# PCB-CMB-3.net
KiCad netlist of a schematic drawn in EAGLE
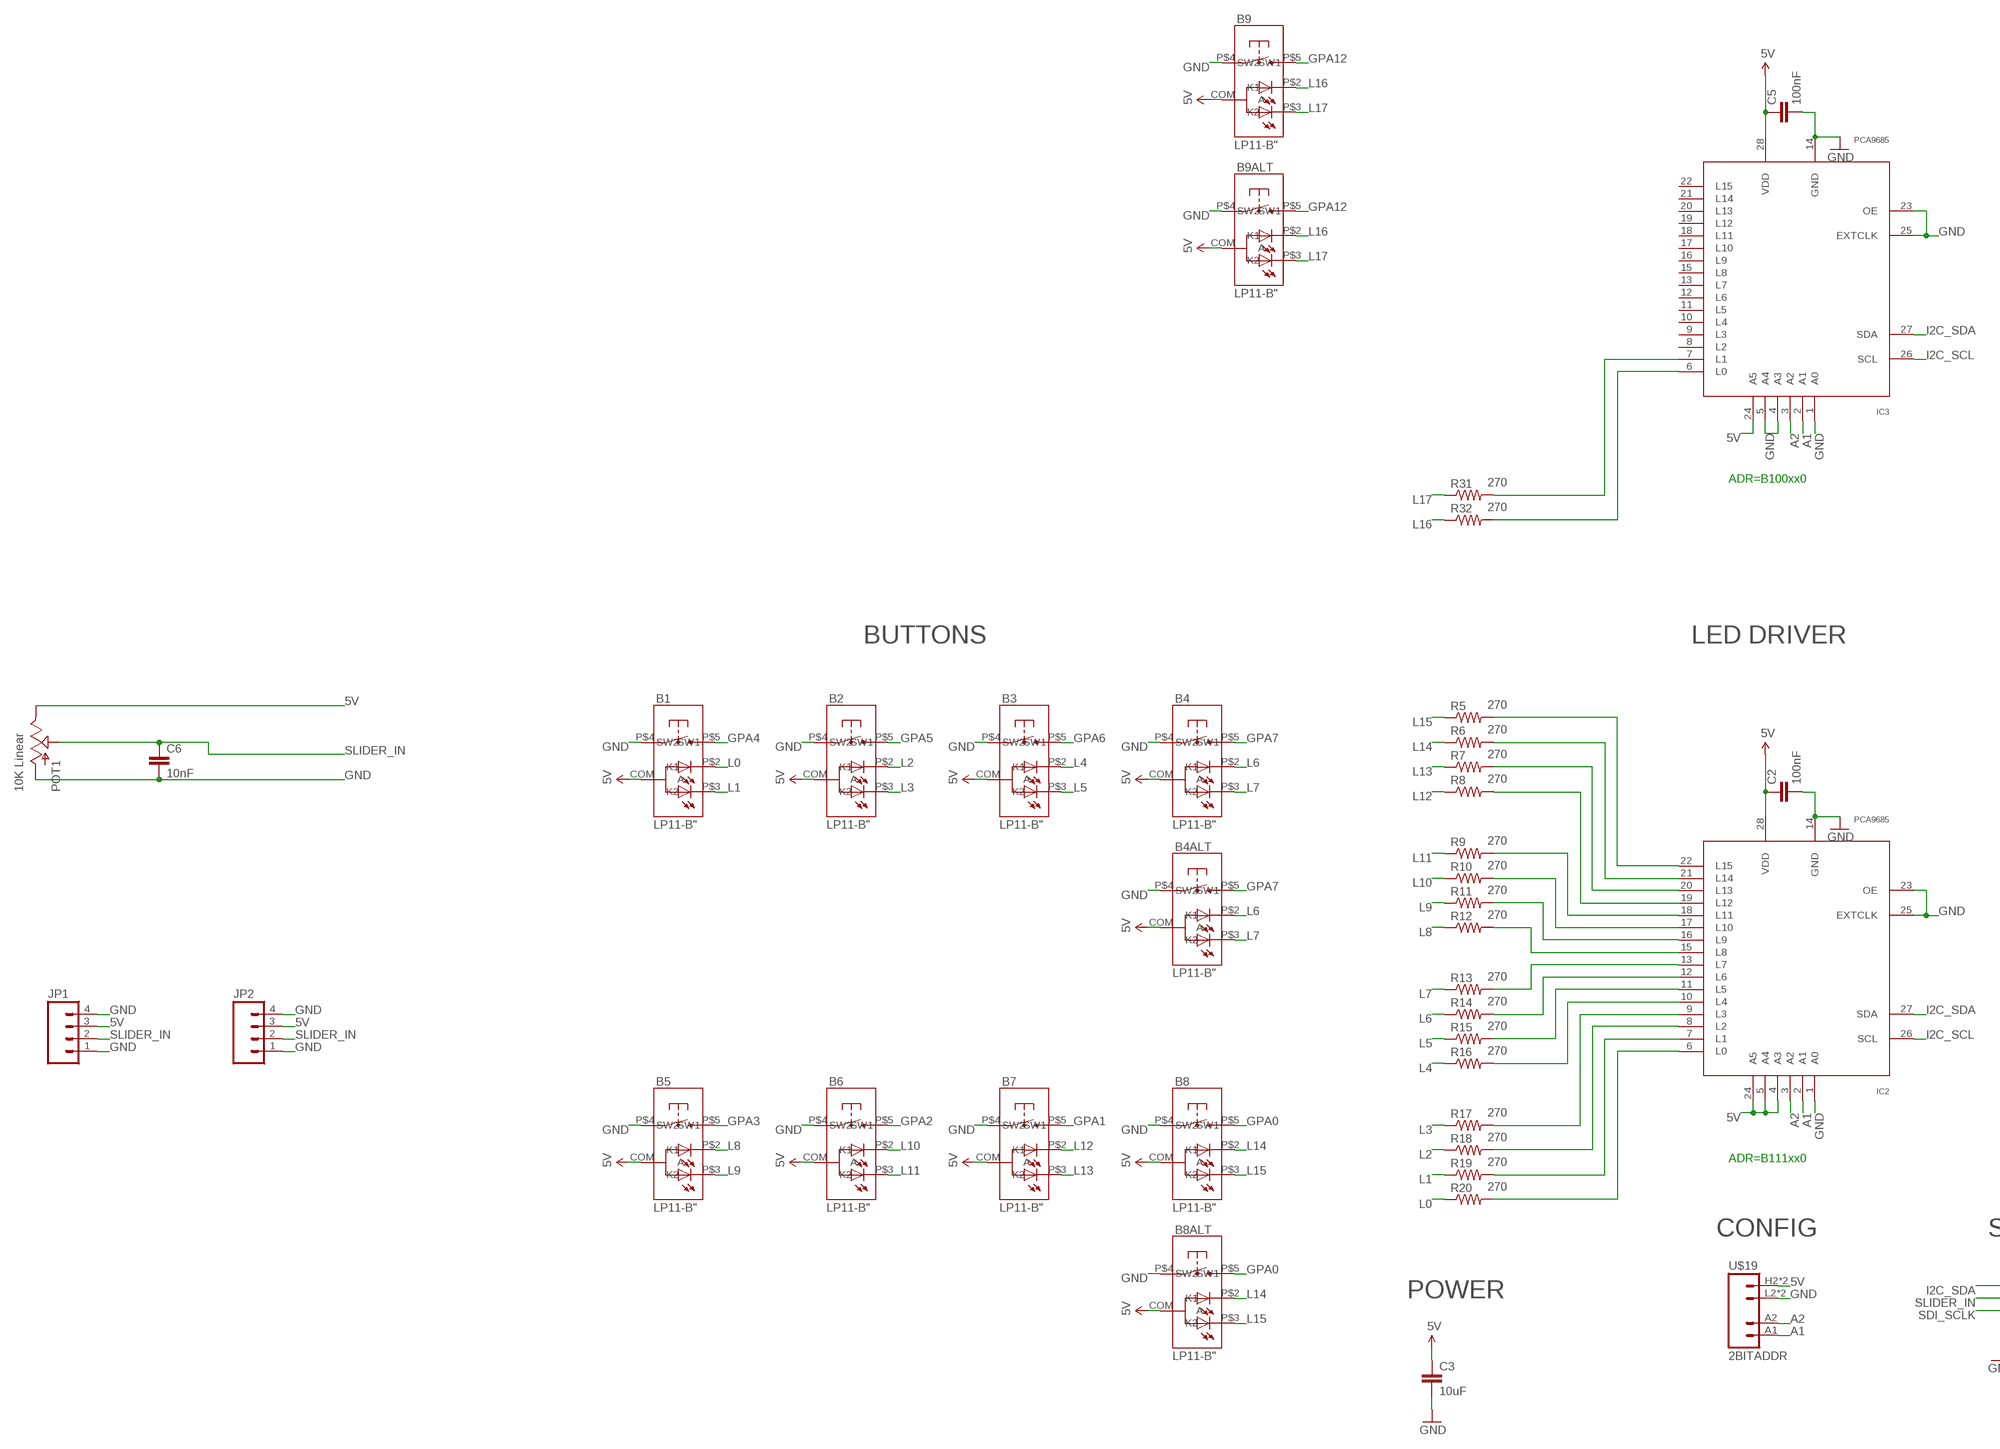
[diagram p0: schematic, sheet 1, part 1 of 2]
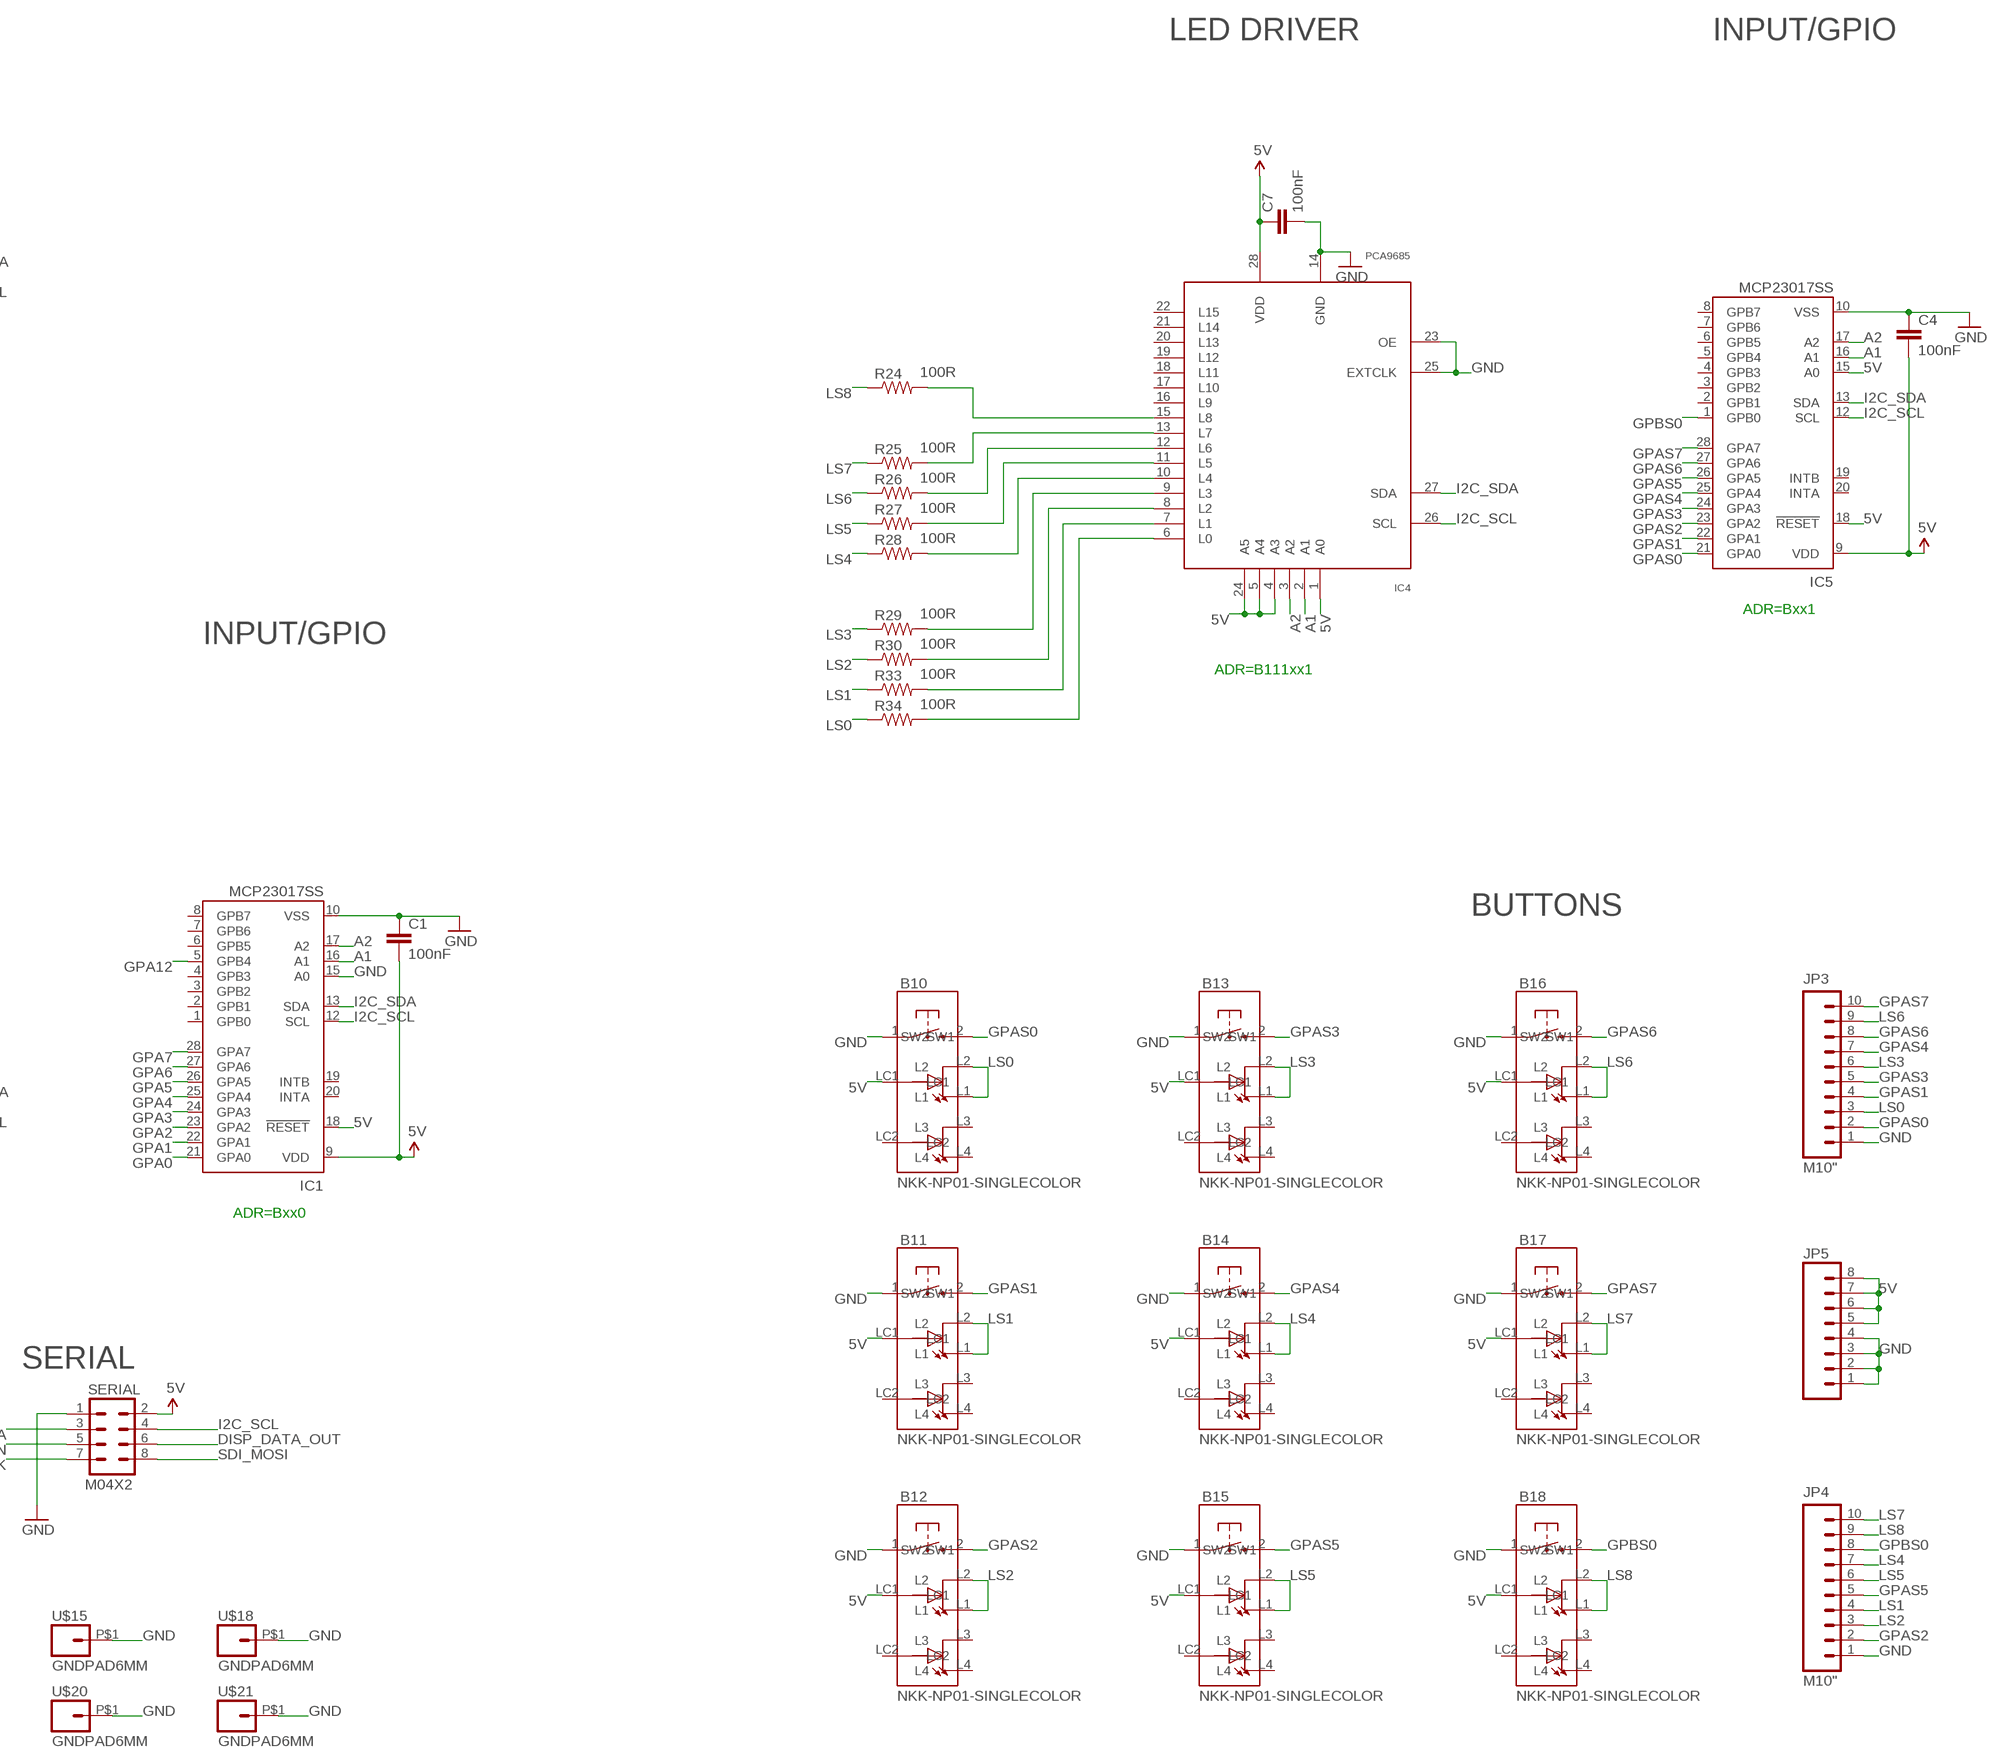
[diagram p1: schematic, sheet 1, part 2 of 2]

(export (version "E")
  (design (tool "Eeschema 10.0.6"))
  (components
    (comp (ref "B1")
      (value "LP11-B\"")
      (footprint "eagle-import:LP11")
      (libsource (lib "eagle-import") (part "LP11-B{dblquote}"))
    )
    (comp (ref "B2")
      (value "LP11-B\"")
      (footprint "eagle-import:LP11")
      (libsource (lib "eagle-import") (part "LP11-B{dblquote}"))
    )
    (comp (ref "B3")
      (value "LP11-B\"")
      (footprint "eagle-import:LP11")
      (libsource (lib "eagle-import") (part "LP11-B{dblquote}"))
    )
    (comp (ref "B4")
      (value "LP11-B\"")
      (footprint "eagle-import:LP11")
      (libsource (lib "eagle-import") (part "LP11-B{dblquote}"))
    )
    (comp (ref "B4ALT")
      (value "LP11-B\"")
      (footprint "eagle-import:LP11")
      (libsource (lib "eagle-import") (part "LP11-B{dblquote}"))
    )
    (comp (ref "B5")
      (value "LP11-B\"")
      (footprint "eagle-import:LP11")
      (libsource (lib "eagle-import") (part "LP11-B{dblquote}"))
    )
    (comp (ref "B6")
      (value "LP11-B\"")
      (footprint "eagle-import:LP11")
      (libsource (lib "eagle-import") (part "LP11-B{dblquote}"))
    )
    (comp (ref "B7")
      (value "LP11-B\"")
      (footprint "eagle-import:LP11")
      (libsource (lib "eagle-import") (part "LP11-B{dblquote}"))
    )
    (comp (ref "B8")
      (value "LP11-B\"")
      (footprint "eagle-import:LP11")
      (libsource (lib "eagle-import") (part "LP11-B{dblquote}"))
    )
    (comp (ref "B8ALT")
      (value "LP11-B\"")
      (footprint "eagle-import:LP11")
      (libsource (lib "eagle-import") (part "LP11-B{dblquote}"))
    )
    (comp (ref "B9")
      (value "LP11-B\"")
      (footprint "eagle-import:LP11")
      (libsource (lib "eagle-import") (part "LP11-B{dblquote}"))
    )
    (comp (ref "B9ALT")
      (value "LP11-B\"")
      (footprint "eagle-import:LP11")
      (libsource (lib "eagle-import") (part "LP11-B{dblquote}"))
    )
    (comp (ref "B10")
      (value "NKK-NP01-SINGLECOLOR")
      (footprint "eagle-import:NKK-NP01")
      (libsource (lib "eagle-import") (part "NKK-NP01-SINGLECOLOR"))
    )
    (comp (ref "B11")
      (value "NKK-NP01-SINGLECOLOR")
      (footprint "eagle-import:NKK-NP01")
      (libsource (lib "eagle-import") (part "NKK-NP01-SINGLECOLOR"))
    )
    (comp (ref "B12")
      (value "NKK-NP01-SINGLECOLOR")
      (footprint "eagle-import:NKK-NP01")
      (libsource (lib "eagle-import") (part "NKK-NP01-SINGLECOLOR"))
    )
    (comp (ref "B13")
      (value "NKK-NP01-SINGLECOLOR")
      (footprint "eagle-import:NKK-NP01")
      (libsource (lib "eagle-import") (part "NKK-NP01-SINGLECOLOR"))
    )
    (comp (ref "B14")
      (value "NKK-NP01-SINGLECOLOR")
      (footprint "eagle-import:NKK-NP01")
      (libsource (lib "eagle-import") (part "NKK-NP01-SINGLECOLOR"))
    )
    (comp (ref "B15")
      (value "NKK-NP01-SINGLECOLOR")
      (footprint "eagle-import:NKK-NP01")
      (libsource (lib "eagle-import") (part "NKK-NP01-SINGLECOLOR"))
    )
    (comp (ref "B16")
      (value "NKK-NP01-SINGLECOLOR")
      (footprint "eagle-import:NKK-NP01")
      (libsource (lib "eagle-import") (part "NKK-NP01-SINGLECOLOR"))
    )
    (comp (ref "B17")
      (value "NKK-NP01-SINGLECOLOR")
      (footprint "eagle-import:NKK-NP01")
      (libsource (lib "eagle-import") (part "NKK-NP01-SINGLECOLOR"))
    )
    (comp (ref "B18")
      (value "NKK-NP01-SINGLECOLOR")
      (footprint "eagle-import:NKK-NP01")
      (libsource (lib "eagle-import") (part "NKK-NP01-SINGLECOLOR"))
    )
    (comp (ref "C1")
      (value "100nF")
      (footprint "eagle-import:0603-CAP")
      (libsource (lib "eagle-import") (part "CAP0603-CAP"))
    )
    (comp (ref "C2")
      (value "100nF")
      (footprint "eagle-import:0603-CAP")
      (libsource (lib "eagle-import") (part "CAP0603-CAP"))
    )
    (comp (ref "C3")
      (value "10uF")
      (footprint "eagle-import:0805")
      (libsource (lib "eagle-import") (part "CAP0805"))
    )
    (comp (ref "C4")
      (value "100nF")
      (footprint "eagle-import:0603-CAP")
      (libsource (lib "eagle-import") (part "CAP0603-CAP"))
    )
    (comp (ref "C5")
      (value "100nF")
      (footprint "eagle-import:0603-CAP")
      (libsource (lib "eagle-import") (part "CAP0603-CAP"))
    )
    (comp (ref "C6")
      (value "10nF")
      (footprint "eagle-import:0603-CAP")
      (libsource (lib "eagle-import") (part "CAP0603-CAP"))
    )
    (comp (ref "C7")
      (value "100nF")
      (footprint "eagle-import:0603-CAP")
      (libsource (lib "eagle-import") (part "CAP0603-CAP"))
    )
    (comp (ref "IC1")
      (value "MCP23017SS")
      (footprint "eagle-import:SSOP28")
      (fields
        (field (name "MF") "MICROCHIP")
        (field (name "MPN") "MCP23017-E/SS")
        (field (name "MPN_1") "MCP23017-E/SS")
        (field (name "OC_FARNELL") "1467674")
        (field (name "OC_NEWARK") "31K2960")
      )
      (libsource (lib "eagle-import") (part "MCP23017SS"))
    )
    (comp (ref "IC2")
      (value "PCA9685")
      (footprint "eagle-import:TSSOP28")
      (libsource (lib "eagle-import") (part "PCA9685"))
    )
    (comp (ref "IC3")
      (value "PCA9685")
      (footprint "eagle-import:TSSOP28")
      (libsource (lib "eagle-import") (part "PCA9685"))
    )
    (comp (ref "IC4")
      (value "PCA9685")
      (footprint "eagle-import:TSSOP28")
      (libsource (lib "eagle-import") (part "PCA9685"))
    )
    (comp (ref "IC5")
      (value "MCP23017SS")
      (footprint "eagle-import:SSOP28")
      (fields
        (field (name "MF") "MICROCHIP")
        (field (name "MPN") "MCP23017-E/SS")
        (field (name "MPN_1") "MCP23017-E/SS")
        (field (name "OC_FARNELL") "1467674")
        (field (name "OC_NEWARK") "31K2960")
      )
      (libsource (lib "eagle-import") (part "MCP23017SS"))
    )
    (comp (ref "JP1")
      (value "M04PTH")
      (footprint "eagle-import:1X04")
      (libsource (lib "eagle-import") (part "M04PTH"))
    )
    (comp (ref "JP2")
      (value "M04PTH")
      (footprint "eagle-import:1X04")
      (libsource (lib "eagle-import") (part "M04PTH"))
    )
    (comp (ref "JP3")
      (value "M10\"")
      (footprint "eagle-import:1X10")
      (libsource (lib "eagle-import") (part "M10{dblquote}"))
    )
    (comp (ref "JP4")
      (value "M10\"")
      (footprint "eagle-import:1X10")
      (libsource (lib "eagle-import") (part "M10{dblquote}"))
    )
    (comp (ref "JP5")
      (value "M08LOCK")
      (footprint "eagle-import:1X08_LOCK")
      (libsource (lib "eagle-import") (part "M08LOCK"))
    )
    (comp (ref "POT1")
      (value "10K Linear")
      (footprint "eagle-import:SLIDER20")
      (libsource (lib "eagle-import") (part "SLIDER20"))
    )
    (comp (ref "R5")
      (value "270")
      (footprint "eagle-import:0603-RES")
      (libsource (lib "eagle-import") (part "RESISTOR0603-RES"))
    )
    (comp (ref "R6")
      (value "270")
      (footprint "eagle-import:0603-RES")
      (libsource (lib "eagle-import") (part "RESISTOR0603-RES"))
    )
    (comp (ref "R7")
      (value "270")
      (footprint "eagle-import:0603-RES")
      (libsource (lib "eagle-import") (part "RESISTOR0603-RES"))
    )
    (comp (ref "R8")
      (value "270")
      (footprint "eagle-import:0603-RES")
      (libsource (lib "eagle-import") (part "RESISTOR0603-RES"))
    )
    (comp (ref "R9")
      (value "270")
      (footprint "eagle-import:0603-RES")
      (libsource (lib "eagle-import") (part "RESISTOR0603-RES"))
    )
    (comp (ref "R10")
      (value "270")
      (footprint "eagle-import:0603-RES")
      (libsource (lib "eagle-import") (part "RESISTOR0603-RES"))
    )
    (comp (ref "R11")
      (value "270")
      (footprint "eagle-import:0603-RES")
      (libsource (lib "eagle-import") (part "RESISTOR0603-RES"))
    )
    (comp (ref "R12")
      (value "270")
      (footprint "eagle-import:0603-RES")
      (libsource (lib "eagle-import") (part "RESISTOR0603-RES"))
    )
    (comp (ref "R13")
      (value "270")
      (footprint "eagle-import:0603-RES")
      (libsource (lib "eagle-import") (part "RESISTOR0603-RES"))
    )
    (comp (ref "R14")
      (value "270")
      (footprint "eagle-import:0603-RES")
      (libsource (lib "eagle-import") (part "RESISTOR0603-RES"))
    )
    (comp (ref "R15")
      (value "270")
      (footprint "eagle-import:0603-RES")
      (libsource (lib "eagle-import") (part "RESISTOR0603-RES"))
    )
    (comp (ref "R16")
      (value "270")
      (footprint "eagle-import:0603-RES")
      (libsource (lib "eagle-import") (part "RESISTOR0603-RES"))
    )
    (comp (ref "R17")
      (value "270")
      (footprint "eagle-import:0603-RES")
      (libsource (lib "eagle-import") (part "RESISTOR0603-RES"))
    )
    (comp (ref "R18")
      (value "270")
      (footprint "eagle-import:0603-RES")
      (libsource (lib "eagle-import") (part "RESISTOR0603-RES"))
    )
    (comp (ref "R19")
      (value "270")
      (footprint "eagle-import:0603-RES")
      (libsource (lib "eagle-import") (part "RESISTOR0603-RES"))
    )
    (comp (ref "R20")
      (value "270")
      (footprint "eagle-import:0603-RES")
      (libsource (lib "eagle-import") (part "RESISTOR0603-RES"))
    )
    (comp (ref "R24")
      (value "100R")
      (footprint "eagle-import:0603-RES")
      (libsource (lib "eagle-import") (part "RESISTOR0603-RES"))
    )
    (comp (ref "R25")
      (value "100R")
      (footprint "eagle-import:0603-RES")
      (libsource (lib "eagle-import") (part "RESISTOR0603-RES"))
    )
    (comp (ref "R26")
      (value "100R")
      (footprint "eagle-import:0603-RES")
      (libsource (lib "eagle-import") (part "RESISTOR0603-RES"))
    )
    (comp (ref "R27")
      (value "100R")
      (footprint "eagle-import:0603-RES")
      (libsource (lib "eagle-import") (part "RESISTOR0603-RES"))
    )
    (comp (ref "R28")
      (value "100R")
      (footprint "eagle-import:0603-RES")
      (libsource (lib "eagle-import") (part "RESISTOR0603-RES"))
    )
    (comp (ref "R29")
      (value "100R")
      (footprint "eagle-import:0603-RES")
      (libsource (lib "eagle-import") (part "RESISTOR0603-RES"))
    )
    (comp (ref "R30")
      (value "100R")
      (footprint "eagle-import:0603-RES")
      (libsource (lib "eagle-import") (part "RESISTOR0603-RES"))
    )
    (comp (ref "R31")
      (value "270")
      (footprint "eagle-import:0603-RES")
      (libsource (lib "eagle-import") (part "RESISTOR0603-RES"))
    )
    (comp (ref "R32")
      (value "270")
      (footprint "eagle-import:0603-RES")
      (libsource (lib "eagle-import") (part "RESISTOR0603-RES"))
    )
    (comp (ref "R33")
      (value "100R")
      (footprint "eagle-import:0603-RES")
      (libsource (lib "eagle-import") (part "RESISTOR0603-RES"))
    )
    (comp (ref "R34")
      (value "100R")
      (footprint "eagle-import:0603-RES")
      (libsource (lib "eagle-import") (part "RESISTOR0603-RES"))
    )
    (comp (ref "SERIAL")
      (value "M04X2")
      (footprint "eagle-import:2X4")
      (libsource (lib "eagle-import") (part "M04X2"))
    )
    (comp (ref "U$15")
      (value "GNDPAD6MM")
      (footprint "eagle-import:3.2MMPAD6MM")
      (libsource (lib "eagle-import") (part "GNDPAD6MM"))
    )
    (comp (ref "U$18")
      (value "GNDPAD6MM")
      (footprint "eagle-import:3.2MMPAD6MM")
      (libsource (lib "eagle-import") (part "GNDPAD6MM"))
    )
    (comp (ref "U$19")
      (value "2BITADDR")
      (footprint "eagle-import:2BITADDR")
      (libsource (lib "eagle-import") (part "2BITADDR"))
    )
    (comp (ref "U$20")
      (value "GNDPAD6MM")
      (footprint "eagle-import:3.2MMPAD6MM")
      (libsource (lib "eagle-import") (part "GNDPAD6MM"))
    )
    (comp (ref "U$21")
      (value "GNDPAD6MM")
      (footprint "eagle-import:3.2MMPAD6MM")
      (libsource (lib "eagle-import") (part "GNDPAD6MM"))
    )
  )
  (nets
    (net (code "1") (name "5V") (class "Default")
      (node (ref "B1") (pin "COM") (pinfunction "A_COM") (pintype "bidirectional"))
      (node (ref "B10") (pin "LC1") (pinfunction "LC1_LC1") (pintype "bidirectional"))
      (node (ref "B11") (pin "LC1") (pinfunction "LC1_LC1") (pintype "bidirectional"))
      (node (ref "B12") (pin "LC1") (pinfunction "LC1_LC1") (pintype "bidirectional"))
      (node (ref "B13") (pin "LC1") (pinfunction "LC1_LC1") (pintype "bidirectional"))
      (node (ref "B14") (pin "LC1") (pinfunction "LC1_LC1") (pintype "bidirectional"))
      (node (ref "B15") (pin "LC1") (pinfunction "LC1_LC1") (pintype "bidirectional"))
      (node (ref "B16") (pin "LC1") (pinfunction "LC1_LC1") (pintype "bidirectional"))
      (node (ref "B17") (pin "LC1") (pinfunction "LC1_LC1") (pintype "bidirectional"))
      (node (ref "B18") (pin "LC1") (pinfunction "LC1_LC1") (pintype "bidirectional"))
      (node (ref "B2") (pin "COM") (pinfunction "A_COM") (pintype "bidirectional"))
      (node (ref "B3") (pin "COM") (pinfunction "A_COM") (pintype "bidirectional"))
      (node (ref "B4") (pin "COM") (pinfunction "A_COM") (pintype "bidirectional"))
      (node (ref "B4ALT") (pin "COM") (pinfunction "A_COM") (pintype "bidirectional"))
      (node (ref "B5") (pin "COM") (pinfunction "A_COM") (pintype "bidirectional"))
      (node (ref "B6") (pin "COM") (pinfunction "A_COM") (pintype "bidirectional"))
      (node (ref "B7") (pin "COM") (pinfunction "A_COM") (pintype "bidirectional"))
      (node (ref "B8") (pin "COM") (pinfunction "A_COM") (pintype "bidirectional"))
      (node (ref "B8ALT") (pin "COM") (pinfunction "A_COM") (pintype "bidirectional"))
      (node (ref "B9") (pin "COM") (pinfunction "A_COM") (pintype "bidirectional"))
      (node (ref "B9ALT") (pin "COM") (pinfunction "A_COM") (pintype "bidirectional"))
      (node (ref "C1") (pin "2") (pinfunction "2_2") (pintype "passive"))
      (node (ref "C2") (pin "1") (pinfunction "1_1") (pintype "passive"))
      (node (ref "C3") (pin "1") (pinfunction "1_1") (pintype "passive"))
      (node (ref "C4") (pin "2") (pinfunction "2_2") (pintype "passive"))
      (node (ref "C5") (pin "1") (pinfunction "1_1") (pintype "passive"))
      (node (ref "C7") (pin "1") (pinfunction "1_1") (pintype "passive"))
      (node (ref "IC1") (pin "18") (pinfunction "~{RESET}_18") (pintype "input"))
      (node (ref "IC1") (pin "9") (pinfunction "VDD_9") (pintype "power_in"))
      (node (ref "IC2") (pin "24") (pinfunction "A5_24") (pintype "input"))
      (node (ref "IC2") (pin "28") (pinfunction "VDD_28") (pintype "power_in"))
      (node (ref "IC2") (pin "4") (pinfunction "A3_4") (pintype "input"))
      (node (ref "IC2") (pin "5") (pinfunction "A4_5") (pintype "input"))
      (node (ref "IC3") (pin "24") (pinfunction "A5_24") (pintype "input"))
      (node (ref "IC3") (pin "28") (pinfunction "VDD_28") (pintype "power_in"))
      (node (ref "IC4") (pin "1") (pinfunction "A0_1") (pintype "input"))
      (node (ref "IC4") (pin "24") (pinfunction "A5_24") (pintype "input"))
      (node (ref "IC4") (pin "28") (pinfunction "VDD_28") (pintype "power_in"))
      (node (ref "IC4") (pin "4") (pinfunction "A3_4") (pintype "input"))
      (node (ref "IC4") (pin "5") (pinfunction "A4_5") (pintype "input"))
      (node (ref "IC5") (pin "15") (pinfunction "A0_15") (pintype "input"))
      (node (ref "IC5") (pin "18") (pinfunction "~{RESET}_18") (pintype "input"))
      (node (ref "IC5") (pin "9") (pinfunction "VDD_9") (pintype "power_in"))
      (node (ref "JP1") (pin "3") (pinfunction "3_3") (pintype "passive"))
      (node (ref "JP2") (pin "3") (pinfunction "3_3") (pintype "passive"))
      (node (ref "JP5") (pin "5") (pinfunction "5_5") (pintype "passive"))
      (node (ref "JP5") (pin "6") (pinfunction "6_6") (pintype "passive"))
      (node (ref "JP5") (pin "7") (pinfunction "7_7") (pintype "passive"))
      (node (ref "JP5") (pin "8") (pinfunction "8_8") (pintype "passive"))
      (node (ref "POT1") (pin "1") (pinfunction "E_1") (pintype "passive"))
      (node (ref "SERIAL") (pin "2") (pinfunction "2_2") (pintype "passive"))
      (node (ref "U$19") (pin "H2") (pinfunction "VCC_H2") (pintype "passive"))
      (node (ref "U$19") (pin "H3") (pinfunction "VCC_H3") (pintype "passive"))
    )
    (net (code "2") (name "A1") (class "Default")
      (node (ref "IC1") (pin "16") (pinfunction "A1_16") (pintype "input"))
      (node (ref "IC2") (pin "2") (pinfunction "A1_2") (pintype "input"))
      (node (ref "IC3") (pin "2") (pinfunction "A1_2") (pintype "input"))
      (node (ref "IC4") (pin "2") (pinfunction "A1_2") (pintype "input"))
      (node (ref "IC5") (pin "16") (pinfunction "A1_16") (pintype "input"))
      (node (ref "U$19") (pin "A1") (pinfunction "A1_A1") (pintype "passive"))
    )
    (net (code "3") (name "A2") (class "Default")
      (node (ref "IC1") (pin "17") (pinfunction "A2_17") (pintype "input"))
      (node (ref "IC2") (pin "3") (pinfunction "A2_3") (pintype "input"))
      (node (ref "IC3") (pin "3") (pinfunction "A2_3") (pintype "input"))
      (node (ref "IC4") (pin "3") (pinfunction "A2_3") (pintype "input"))
      (node (ref "IC5") (pin "17") (pinfunction "A2_17") (pintype "input"))
      (node (ref "U$19") (pin "A2") (pinfunction "A2_A2") (pintype "passive"))
    )
    (net (code "4") (name "DISP_DATA_OUT") (class "Default")
      (node (ref "SERIAL") (pin "6") (pinfunction "6_6") (pintype "passive"))
    )
    (net (code "5") (name "GND") (class "Default")
      (node (ref "B1") (pin "P$4") (pinfunction "SW1_P$4") (pintype "bidirectional"))
      (node (ref "B10") (pin "1") (pinfunction "SW1_1") (pintype "bidirectional"))
      (node (ref "B11") (pin "1") (pinfunction "SW1_1") (pintype "bidirectional"))
      (node (ref "B12") (pin "1") (pinfunction "SW1_1") (pintype "bidirectional"))
      (node (ref "B13") (pin "1") (pinfunction "SW1_1") (pintype "bidirectional"))
      (node (ref "B14") (pin "1") (pinfunction "SW1_1") (pintype "bidirectional"))
      (node (ref "B15") (pin "1") (pinfunction "SW1_1") (pintype "bidirectional"))
      (node (ref "B16") (pin "1") (pinfunction "SW1_1") (pintype "bidirectional"))
      (node (ref "B17") (pin "1") (pinfunction "SW1_1") (pintype "bidirectional"))
      (node (ref "B18") (pin "1") (pinfunction "SW1_1") (pintype "bidirectional"))
      (node (ref "B2") (pin "P$4") (pinfunction "SW1_P$4") (pintype "bidirectional"))
      (node (ref "B3") (pin "P$4") (pinfunction "SW1_P$4") (pintype "bidirectional"))
      (node (ref "B4") (pin "P$4") (pinfunction "SW1_P$4") (pintype "bidirectional"))
      (node (ref "B4ALT") (pin "P$4") (pinfunction "SW1_P$4") (pintype "bidirectional"))
      (node (ref "B5") (pin "P$4") (pinfunction "SW1_P$4") (pintype "bidirectional"))
      (node (ref "B6") (pin "P$4") (pinfunction "SW1_P$4") (pintype "bidirectional"))
      (node (ref "B7") (pin "P$4") (pinfunction "SW1_P$4") (pintype "bidirectional"))
      (node (ref "B8") (pin "P$4") (pinfunction "SW1_P$4") (pintype "bidirectional"))
      (node (ref "B8ALT") (pin "P$4") (pinfunction "SW1_P$4") (pintype "bidirectional"))
      (node (ref "B9") (pin "P$4") (pinfunction "SW1_P$4") (pintype "bidirectional"))
      (node (ref "B9ALT") (pin "P$4") (pinfunction "SW1_P$4") (pintype "bidirectional"))
      (node (ref "C1") (pin "1") (pinfunction "1_1") (pintype "passive"))
      (node (ref "C2") (pin "2") (pinfunction "2_2") (pintype "passive"))
      (node (ref "C3") (pin "2") (pinfunction "2_2") (pintype "passive"))
      (node (ref "C4") (pin "1") (pinfunction "1_1") (pintype "passive"))
      (node (ref "C5") (pin "2") (pinfunction "2_2") (pintype "passive"))
      (node (ref "C6") (pin "2") (pinfunction "2_2") (pintype "passive"))
      (node (ref "C7") (pin "2") (pinfunction "2_2") (pintype "passive"))
      (node (ref "IC1") (pin "10") (pinfunction "VSS_10") (pintype "power_in"))
      (node (ref "IC1") (pin "15") (pinfunction "A0_15") (pintype "input"))
      (node (ref "IC2") (pin "1") (pinfunction "A0_1") (pintype "input"))
      (node (ref "IC2") (pin "14") (pinfunction "GND_14") (pintype "power_in"))
      (node (ref "IC2") (pin "23") (pinfunction "OE_23") (pintype "input"))
      (node (ref "IC2") (pin "25") (pinfunction "EXTCLK_25") (pintype "input"))
      (node (ref "IC3") (pin "1") (pinfunction "A0_1") (pintype "input"))
      (node (ref "IC3") (pin "14") (pinfunction "GND_14") (pintype "power_in"))
      (node (ref "IC3") (pin "23") (pinfunction "OE_23") (pintype "input"))
      (node (ref "IC3") (pin "25") (pinfunction "EXTCLK_25") (pintype "input"))
      (node (ref "IC3") (pin "4") (pinfunction "A3_4") (pintype "input"))
      (node (ref "IC3") (pin "5") (pinfunction "A4_5") (pintype "input"))
      (node (ref "IC4") (pin "14") (pinfunction "GND_14") (pintype "power_in"))
      (node (ref "IC4") (pin "23") (pinfunction "OE_23") (pintype "input"))
      (node (ref "IC4") (pin "25") (pinfunction "EXTCLK_25") (pintype "input"))
      (node (ref "IC5") (pin "10") (pinfunction "VSS_10") (pintype "power_in"))
      (node (ref "JP1") (pin "1") (pinfunction "1_1") (pintype "passive"))
      (node (ref "JP1") (pin "4") (pinfunction "4_4") (pintype "passive"))
      (node (ref "JP2") (pin "1") (pinfunction "1_1") (pintype "passive"))
      (node (ref "JP2") (pin "4") (pinfunction "4_4") (pintype "passive"))
      (node (ref "JP3") (pin "1") (pinfunction "1_1") (pintype "passive"))
      (node (ref "JP4") (pin "1") (pinfunction "1_1") (pintype "passive"))
      (node (ref "JP5") (pin "1") (pinfunction "1_1") (pintype "passive"))
      (node (ref "JP5") (pin "2") (pinfunction "2_2") (pintype "passive"))
      (node (ref "JP5") (pin "3") (pinfunction "3_3") (pintype "passive"))
      (node (ref "JP5") (pin "4") (pinfunction "4_4") (pintype "passive"))
      (node (ref "POT1") (pin "3") (pinfunction "A_3") (pintype "passive"))
      (node (ref "SERIAL") (pin "1") (pinfunction "1_1") (pintype "passive"))
      (node (ref "U$15") (pin "P$1") (pinfunction "1_P$1") (pintype "passive"))
      (node (ref "U$18") (pin "P$1") (pinfunction "1_P$1") (pintype "passive"))
      (node (ref "U$19") (pin "L2") (pinfunction "GND_L2") (pintype "passive"))
      (node (ref "U$19") (pin "L3") (pinfunction "GND_L3") (pintype "passive"))
      (node (ref "U$20") (pin "P$1") (pinfunction "1_P$1") (pintype "passive"))
      (node (ref "U$21") (pin "P$1") (pinfunction "1_P$1") (pintype "passive"))
    )
    (net (code "6") (name "GPA0") (class "Default")
      (node (ref "B8") (pin "P$5") (pinfunction "SW2_P$5") (pintype "bidirectional"))
      (node (ref "B8ALT") (pin "P$5") (pinfunction "SW2_P$5") (pintype "bidirectional"))
      (node (ref "IC1") (pin "21") (pinfunction "GPA0_21") (pintype "bidirectional"))
    )
    (net (code "7") (name "GPA1") (class "Default")
      (node (ref "B7") (pin "P$5") (pinfunction "SW2_P$5") (pintype "bidirectional"))
      (node (ref "IC1") (pin "22") (pinfunction "GPA1_22") (pintype "bidirectional"))
    )
    (net (code "8") (name "GPA2") (class "Default")
      (node (ref "B6") (pin "P$5") (pinfunction "SW2_P$5") (pintype "bidirectional"))
      (node (ref "IC1") (pin "23") (pinfunction "GPA2_23") (pintype "bidirectional"))
    )
    (net (code "9") (name "GPA3") (class "Default")
      (node (ref "B5") (pin "P$5") (pinfunction "SW2_P$5") (pintype "bidirectional"))
      (node (ref "IC1") (pin "24") (pinfunction "GPA3_24") (pintype "bidirectional"))
    )
    (net (code "10") (name "GPA4") (class "Default")
      (node (ref "B1") (pin "P$5") (pinfunction "SW2_P$5") (pintype "bidirectional"))
      (node (ref "IC1") (pin "25") (pinfunction "GPA4_25") (pintype "bidirectional"))
    )
    (net (code "11") (name "GPA5") (class "Default")
      (node (ref "B2") (pin "P$5") (pinfunction "SW2_P$5") (pintype "bidirectional"))
      (node (ref "IC1") (pin "26") (pinfunction "GPA5_26") (pintype "bidirectional"))
    )
    (net (code "12") (name "GPA6") (class "Default")
      (node (ref "B3") (pin "P$5") (pinfunction "SW2_P$5") (pintype "bidirectional"))
      (node (ref "IC1") (pin "27") (pinfunction "GPA6_27") (pintype "bidirectional"))
    )
    (net (code "13") (name "GPA7") (class "Default")
      (node (ref "B4") (pin "P$5") (pinfunction "SW2_P$5") (pintype "bidirectional"))
      (node (ref "B4ALT") (pin "P$5") (pinfunction "SW2_P$5") (pintype "bidirectional"))
      (node (ref "IC1") (pin "28") (pinfunction "GPA7_28") (pintype "bidirectional"))
    )
    (net (code "14") (name "GPA12") (class "Default")
      (node (ref "B9") (pin "P$5") (pinfunction "SW2_P$5") (pintype "bidirectional"))
      (node (ref "B9ALT") (pin "P$5") (pinfunction "SW2_P$5") (pintype "bidirectional"))
      (node (ref "IC1") (pin "5") (pinfunction "GPB4_5") (pintype "bidirectional"))
    )
    (net (code "15") (name "GPAS0") (class "Default")
      (node (ref "B10") (pin "2") (pinfunction "SW2_2") (pintype "bidirectional"))
      (node (ref "IC5") (pin "21") (pinfunction "GPA0_21") (pintype "bidirectional"))
      (node (ref "JP3") (pin "2") (pinfunction "2_2") (pintype "passive"))
    )
    (net (code "16") (name "GPAS1") (class "Default")
      (node (ref "B11") (pin "2") (pinfunction "SW2_2") (pintype "bidirectional"))
      (node (ref "IC5") (pin "22") (pinfunction "GPA1_22") (pintype "bidirectional"))
      (node (ref "JP3") (pin "4") (pinfunction "4_4") (pintype "passive"))
    )
    (net (code "17") (name "GPAS2") (class "Default")
      (node (ref "B12") (pin "2") (pinfunction "SW2_2") (pintype "bidirectional"))
      (node (ref "IC5") (pin "23") (pinfunction "GPA2_23") (pintype "bidirectional"))
      (node (ref "JP4") (pin "2") (pinfunction "2_2") (pintype "passive"))
    )
    (net (code "18") (name "GPAS3") (class "Default")
      (node (ref "B13") (pin "2") (pinfunction "SW2_2") (pintype "bidirectional"))
      (node (ref "IC5") (pin "24") (pinfunction "GPA3_24") (pintype "bidirectional"))
      (node (ref "JP3") (pin "5") (pinfunction "5_5") (pintype "passive"))
    )
    (net (code "19") (name "GPAS4") (class "Default")
      (node (ref "B14") (pin "2") (pinfunction "SW2_2") (pintype "bidirectional"))
      (node (ref "IC5") (pin "25") (pinfunction "GPA4_25") (pintype "bidirectional"))
      (node (ref "JP3") (pin "7") (pinfunction "7_7") (pintype "passive"))
    )
    (net (code "20") (name "GPAS5") (class "Default")
      (node (ref "B15") (pin "2") (pinfunction "SW2_2") (pintype "bidirectional"))
      (node (ref "IC5") (pin "26") (pinfunction "GPA5_26") (pintype "bidirectional"))
      (node (ref "JP4") (pin "5") (pinfunction "5_5") (pintype "passive"))
    )
    (net (code "21") (name "GPAS6") (class "Default")
      (node (ref "B16") (pin "2") (pinfunction "SW2_2") (pintype "bidirectional"))
      (node (ref "IC5") (pin "27") (pinfunction "GPA6_27") (pintype "bidirectional"))
      (node (ref "JP3") (pin "8") (pinfunction "8_8") (pintype "passive"))
    )
    (net (code "22") (name "GPAS7") (class "Default")
      (node (ref "B17") (pin "2") (pinfunction "SW2_2") (pintype "bidirectional"))
      (node (ref "IC5") (pin "28") (pinfunction "GPA7_28") (pintype "bidirectional"))
      (node (ref "JP3") (pin "10") (pinfunction "10_10") (pintype "passive"))
    )
    (net (code "23") (name "GPBS0") (class "Default")
      (node (ref "B18") (pin "2") (pinfunction "SW2_2") (pintype "bidirectional"))
      (node (ref "IC5") (pin "1") (pinfunction "GPB0_1") (pintype "bidirectional"))
      (node (ref "JP4") (pin "8") (pinfunction "8_8") (pintype "passive"))
    )
    (net (code "24") (name "I2C_SCL") (class "Default")
      (node (ref "IC1") (pin "12") (pinfunction "SCL_12") (pintype "input"))
      (node (ref "IC2") (pin "26") (pinfunction "SCL_26") (pintype "input"))
      (node (ref "IC3") (pin "26") (pinfunction "SCL_26") (pintype "input"))
      (node (ref "IC4") (pin "26") (pinfunction "SCL_26") (pintype "input"))
      (node (ref "IC5") (pin "12") (pinfunction "SCL_12") (pintype "input"))
      (node (ref "SERIAL") (pin "4") (pinfunction "4_4") (pintype "passive"))
    )
    (net (code "25") (name "I2C_SDA") (class "Default")
      (node (ref "IC1") (pin "13") (pinfunction "SDA_13") (pintype "bidirectional"))
      (node (ref "IC2") (pin "27") (pinfunction "SDA_27") (pintype "input"))
      (node (ref "IC3") (pin "27") (pinfunction "SDA_27") (pintype "input"))
      (node (ref "IC4") (pin "27") (pinfunction "SDA_27") (pintype "input"))
      (node (ref "IC5") (pin "13") (pinfunction "SDA_13") (pintype "bidirectional"))
      (node (ref "SERIAL") (pin "3") (pinfunction "3_3") (pintype "passive"))
    )
    (net (code "26") (name "L0") (class "Default")
      (node (ref "B1") (pin "P$2") (pinfunction "K1_P$2") (pintype "bidirectional"))
      (node (ref "R20") (pin "1") (pinfunction "1_1") (pintype "passive"))
    )
    (net (code "27") (name "L1") (class "Default")
      (node (ref "B1") (pin "P$3") (pinfunction "K2_P$3") (pintype "bidirectional"))
      (node (ref "R19") (pin "1") (pinfunction "1_1") (pintype "passive"))
    )
    (net (code "28") (name "L2") (class "Default")
      (node (ref "B2") (pin "P$2") (pinfunction "K1_P$2") (pintype "bidirectional"))
      (node (ref "R18") (pin "1") (pinfunction "1_1") (pintype "passive"))
    )
    (net (code "29") (name "L3") (class "Default")
      (node (ref "B2") (pin "P$3") (pinfunction "K2_P$3") (pintype "bidirectional"))
      (node (ref "R17") (pin "1") (pinfunction "1_1") (pintype "passive"))
    )
    (net (code "30") (name "L4") (class "Default")
      (node (ref "B3") (pin "P$2") (pinfunction "K1_P$2") (pintype "bidirectional"))
      (node (ref "R16") (pin "1") (pinfunction "1_1") (pintype "passive"))
    )
    (net (code "31") (name "L5") (class "Default")
      (node (ref "B3") (pin "P$3") (pinfunction "K2_P$3") (pintype "bidirectional"))
      (node (ref "R15") (pin "1") (pinfunction "1_1") (pintype "passive"))
    )
    (net (code "32") (name "L6") (class "Default")
      (node (ref "B4") (pin "P$2") (pinfunction "K1_P$2") (pintype "bidirectional"))
      (node (ref "B4ALT") (pin "P$2") (pinfunction "K1_P$2") (pintype "bidirectional"))
      (node (ref "R14") (pin "1") (pinfunction "1_1") (pintype "passive"))
    )
    (net (code "33") (name "L7") (class "Default")
      (node (ref "B4") (pin "P$3") (pinfunction "K2_P$3") (pintype "bidirectional"))
      (node (ref "B4ALT") (pin "P$3") (pinfunction "K2_P$3") (pintype "bidirectional"))
      (node (ref "R13") (pin "1") (pinfunction "1_1") (pintype "passive"))
    )
    (net (code "34") (name "L8") (class "Default")
      (node (ref "B5") (pin "P$2") (pinfunction "K1_P$2") (pintype "bidirectional"))
      (node (ref "R12") (pin "1") (pinfunction "1_1") (pintype "passive"))
    )
    (net (code "35") (name "L9") (class "Default")
      (node (ref "B5") (pin "P$3") (pinfunction "K2_P$3") (pintype "bidirectional"))
      (node (ref "R11") (pin "1") (pinfunction "1_1") (pintype "passive"))
    )
    (net (code "36") (name "L10") (class "Default")
      (node (ref "B6") (pin "P$2") (pinfunction "K1_P$2") (pintype "bidirectional"))
      (node (ref "R10") (pin "1") (pinfunction "1_1") (pintype "passive"))
    )
    (net (code "37") (name "L11") (class "Default")
      (node (ref "B6") (pin "P$3") (pinfunction "K2_P$3") (pintype "bidirectional"))
      (node (ref "R9") (pin "1") (pinfunction "1_1") (pintype "passive"))
    )
    (net (code "38") (name "L12") (class "Default")
      (node (ref "B7") (pin "P$2") (pinfunction "K1_P$2") (pintype "bidirectional"))
      (node (ref "R8") (pin "1") (pinfunction "1_1") (pintype "passive"))
    )
    (net (code "39") (name "L13") (class "Default")
      (node (ref "B7") (pin "P$3") (pinfunction "K2_P$3") (pintype "bidirectional"))
      (node (ref "R7") (pin "1") (pinfunction "1_1") (pintype "passive"))
    )
    (net (code "40") (name "L14") (class "Default")
      (node (ref "B8") (pin "P$2") (pinfunction "K1_P$2") (pintype "bidirectional"))
      (node (ref "B8ALT") (pin "P$2") (pinfunction "K1_P$2") (pintype "bidirectional"))
      (node (ref "R6") (pin "1") (pinfunction "1_1") (pintype "passive"))
    )
    (net (code "41") (name "L15") (class "Default")
      (node (ref "B8") (pin "P$3") (pinfunction "K2_P$3") (pintype "bidirectional"))
      (node (ref "B8ALT") (pin "P$3") (pinfunction "K2_P$3") (pintype "bidirectional"))
      (node (ref "R5") (pin "1") (pinfunction "1_1") (pintype "passive"))
    )
    (net (code "42") (name "L16") (class "Default")
      (node (ref "B9") (pin "P$2") (pinfunction "K1_P$2") (pintype "bidirectional"))
      (node (ref "B9ALT") (pin "P$2") (pinfunction "K1_P$2") (pintype "bidirectional"))
      (node (ref "R32") (pin "1") (pinfunction "1_1") (pintype "passive"))
    )
    (net (code "43") (name "L17") (class "Default")
      (node (ref "B9") (pin "P$3") (pinfunction "K2_P$3") (pintype "bidirectional"))
      (node (ref "B9ALT") (pin "P$3") (pinfunction "K2_P$3") (pintype "bidirectional"))
      (node (ref "R31") (pin "1") (pinfunction "1_1") (pintype "passive"))
    )
    (net (code "44") (name "LS0") (class "Default")
      (node (ref "B10") (pin "L1") (pinfunction "L1_L1") (pintype "bidirectional"))
      (node (ref "B10") (pin "L2") (pinfunction "L2_L2") (pintype "bidirectional"))
      (node (ref "JP3") (pin "3") (pinfunction "3_3") (pintype "passive"))
      (node (ref "R34") (pin "1") (pinfunction "1_1") (pintype "passive"))
    )
    (net (code "45") (name "LS1") (class "Default")
      (node (ref "B11") (pin "L1") (pinfunction "L1_L1") (pintype "bidirectional"))
      (node (ref "B11") (pin "L2") (pinfunction "L2_L2") (pintype "bidirectional"))
      (node (ref "JP4") (pin "4") (pinfunction "4_4") (pintype "passive"))
      (node (ref "R33") (pin "1") (pinfunction "1_1") (pintype "passive"))
    )
    (net (code "46") (name "LS2") (class "Default")
      (node (ref "B12") (pin "L1") (pinfunction "L1_L1") (pintype "bidirectional"))
      (node (ref "B12") (pin "L2") (pinfunction "L2_L2") (pintype "bidirectional"))
      (node (ref "JP4") (pin "3") (pinfunction "3_3") (pintype "passive"))
      (node (ref "R30") (pin "1") (pinfunction "1_1") (pintype "passive"))
    )
    (net (code "47") (name "LS3") (class "Default")
      (node (ref "B13") (pin "L1") (pinfunction "L1_L1") (pintype "bidirectional"))
      (node (ref "B13") (pin "L2") (pinfunction "L2_L2") (pintype "bidirectional"))
      (node (ref "JP3") (pin "6") (pinfunction "6_6") (pintype "passive"))
      (node (ref "R29") (pin "1") (pinfunction "1_1") (pintype "passive"))
    )
    (net (code "48") (name "LS4") (class "Default")
      (node (ref "B14") (pin "L1") (pinfunction "L1_L1") (pintype "bidirectional"))
      (node (ref "B14") (pin "L2") (pinfunction "L2_L2") (pintype "bidirectional"))
      (node (ref "JP4") (pin "7") (pinfunction "7_7") (pintype "passive"))
      (node (ref "R28") (pin "1") (pinfunction "1_1") (pintype "passive"))
    )
    (net (code "49") (name "LS5") (class "Default")
      (node (ref "B15") (pin "L1") (pinfunction "L1_L1") (pintype "bidirectional"))
      (node (ref "B15") (pin "L2") (pinfunction "L2_L2") (pintype "bidirectional"))
      (node (ref "JP4") (pin "6") (pinfunction "6_6") (pintype "passive"))
      (node (ref "R27") (pin "1") (pinfunction "1_1") (pintype "passive"))
    )
    (net (code "50") (name "LS6") (class "Default")
      (node (ref "B16") (pin "L1") (pinfunction "L1_L1") (pintype "bidirectional"))
      (node (ref "B16") (pin "L2") (pinfunction "L2_L2") (pintype "bidirectional"))
      (node (ref "JP3") (pin "9") (pinfunction "9_9") (pintype "passive"))
      (node (ref "R26") (pin "1") (pinfunction "1_1") (pintype "passive"))
    )
    (net (code "51") (name "LS7") (class "Default")
      (node (ref "B17") (pin "L1") (pinfunction "L1_L1") (pintype "bidirectional"))
      (node (ref "B17") (pin "L2") (pinfunction "L2_L2") (pintype "bidirectional"))
      (node (ref "JP4") (pin "10") (pinfunction "10_10") (pintype "passive"))
      (node (ref "R25") (pin "1") (pinfunction "1_1") (pintype "passive"))
    )
    (net (code "52") (name "LS8") (class "Default")
      (node (ref "B18") (pin "L1") (pinfunction "L1_L1") (pintype "bidirectional"))
      (node (ref "B18") (pin "L2") (pinfunction "L2_L2") (pintype "bidirectional"))
      (node (ref "JP4") (pin "9") (pinfunction "9_9") (pintype "passive"))
      (node (ref "R24") (pin "1") (pinfunction "1_1") (pintype "passive"))
    )
    (net (code "53") (name "Net-(IC2-L0)") (class "Default")
      (node (ref "IC2") (pin "6") (pinfunction "L0_6") (pintype "output"))
      (node (ref "R20") (pin "2") (pinfunction "2_2") (pintype "passive"))
    )
    (net (code "54") (name "Net-(IC2-L1)") (class "Default")
      (node (ref "IC2") (pin "7") (pinfunction "L1_7") (pintype "output"))
      (node (ref "R19") (pin "2") (pinfunction "2_2") (pintype "passive"))
    )
    (net (code "55") (name "Net-(IC2-L2)") (class "Default")
      (node (ref "IC2") (pin "8") (pinfunction "L2_8") (pintype "output"))
      (node (ref "R18") (pin "2") (pinfunction "2_2") (pintype "passive"))
    )
    (net (code "56") (name "Net-(IC2-L3)") (class "Default")
      (node (ref "IC2") (pin "9") (pinfunction "L3_9") (pintype "output"))
      (node (ref "R17") (pin "2") (pinfunction "2_2") (pintype "passive"))
    )
    (net (code "57") (name "Net-(IC2-L4)") (class "Default")
      (node (ref "IC2") (pin "10") (pinfunction "L4_10") (pintype "output"))
      (node (ref "R16") (pin "2") (pinfunction "2_2") (pintype "passive"))
    )
    (net (code "58") (name "Net-(IC2-L5)") (class "Default")
      (node (ref "IC2") (pin "11") (pinfunction "L5_11") (pintype "output"))
      (node (ref "R15") (pin "2") (pinfunction "2_2") (pintype "passive"))
    )
    (net (code "59") (name "Net-(IC2-L6)") (class "Default")
      (node (ref "IC2") (pin "12") (pinfunction "L6_12") (pintype "output"))
      (node (ref "R14") (pin "2") (pinfunction "2_2") (pintype "passive"))
    )
    (net (code "60") (name "Net-(IC2-L7)") (class "Default")
      (node (ref "IC2") (pin "13") (pinfunction "L7_13") (pintype "output"))
      (node (ref "R13") (pin "2") (pinfunction "2_2") (pintype "passive"))
    )
    (net (code "61") (name "Net-(IC2-L8)") (class "Default")
      (node (ref "IC2") (pin "15") (pinfunction "L8_15") (pintype "output"))
      (node (ref "R12") (pin "2") (pinfunction "2_2") (pintype "passive"))
    )
    (net (code "62") (name "Net-(IC2-L9)") (class "Default")
      (node (ref "IC2") (pin "16") (pinfunction "L9_16") (pintype "output"))
      (node (ref "R11") (pin "2") (pinfunction "2_2") (pintype "passive"))
    )
    (net (code "63") (name "Net-(IC2-L10)") (class "Default")
      (node (ref "IC2") (pin "17") (pinfunction "L10_17") (pintype "output"))
      (node (ref "R10") (pin "2") (pinfunction "2_2") (pintype "passive"))
    )
    (net (code "64") (name "Net-(IC2-L11)") (class "Default")
      (node (ref "IC2") (pin "18") (pinfunction "L11_18") (pintype "output"))
      (node (ref "R9") (pin "2") (pinfunction "2_2") (pintype "passive"))
    )
    (net (code "65") (name "Net-(IC2-L12)") (class "Default")
      (node (ref "IC2") (pin "19") (pinfunction "L12_19") (pintype "output"))
      (node (ref "R8") (pin "2") (pinfunction "2_2") (pintype "passive"))
    )
    (net (code "66") (name "Net-(IC2-L13)") (class "Default")
      (node (ref "IC2") (pin "20") (pinfunction "L13_20") (pintype "output"))
      (node (ref "R7") (pin "2") (pinfunction "2_2") (pintype "passive"))
    )
    (net (code "67") (name "Net-(IC2-L14)") (class "Default")
      (node (ref "IC2") (pin "21") (pinfunction "L14_21") (pintype "output"))
      (node (ref "R6") (pin "2") (pinfunction "2_2") (pintype "passive"))
    )
    (net (code "68") (name "Net-(IC2-L15)") (class "Default")
      (node (ref "IC2") (pin "22") (pinfunction "L15_22") (pintype "output"))
      (node (ref "R5") (pin "2") (pinfunction "2_2") (pintype "passive"))
    )
    (net (code "69") (name "Net-(IC3-L0)") (class "Default")
      (node (ref "IC3") (pin "6") (pinfunction "L0_6") (pintype "output"))
      (node (ref "R32") (pin "2") (pinfunction "2_2") (pintype "passive"))
    )
    (net (code "70") (name "Net-(IC3-L1)") (class "Default")
      (node (ref "IC3") (pin "7") (pinfunction "L1_7") (pintype "output"))
      (node (ref "R31") (pin "2") (pinfunction "2_2") (pintype "passive"))
    )
    (net (code "71") (name "Net-(IC4-L0)") (class "Default")
      (node (ref "IC4") (pin "6") (pinfunction "L0_6") (pintype "output"))
      (node (ref "R34") (pin "2") (pinfunction "2_2") (pintype "passive"))
    )
    (net (code "72") (name "Net-(IC4-L1)") (class "Default")
      (node (ref "IC4") (pin "7") (pinfunction "L1_7") (pintype "output"))
      (node (ref "R33") (pin "2") (pinfunction "2_2") (pintype "passive"))
    )
    (net (code "73") (name "Net-(IC4-L2)") (class "Default")
      (node (ref "IC4") (pin "8") (pinfunction "L2_8") (pintype "output"))
      (node (ref "R30") (pin "2") (pinfunction "2_2") (pintype "passive"))
    )
    (net (code "74") (name "Net-(IC4-L3)") (class "Default")
      (node (ref "IC4") (pin "9") (pinfunction "L3_9") (pintype "output"))
      (node (ref "R29") (pin "2") (pinfunction "2_2") (pintype "passive"))
    )
    (net (code "75") (name "Net-(IC4-L4)") (class "Default")
      (node (ref "IC4") (pin "10") (pinfunction "L4_10") (pintype "output"))
      (node (ref "R28") (pin "2") (pinfunction "2_2") (pintype "passive"))
    )
    (net (code "76") (name "Net-(IC4-L5)") (class "Default")
      (node (ref "IC4") (pin "11") (pinfunction "L5_11") (pintype "output"))
      (node (ref "R27") (pin "2") (pinfunction "2_2") (pintype "passive"))
    )
    (net (code "77") (name "Net-(IC4-L6)") (class "Default")
      (node (ref "IC4") (pin "12") (pinfunction "L6_12") (pintype "output"))
      (node (ref "R26") (pin "2") (pinfunction "2_2") (pintype "passive"))
    )
    (net (code "78") (name "Net-(IC4-L7)") (class "Default")
      (node (ref "IC4") (pin "13") (pinfunction "L7_13") (pintype "output"))
      (node (ref "R25") (pin "2") (pinfunction "2_2") (pintype "passive"))
    )
    (net (code "79") (name "Net-(IC4-L8)") (class "Default")
      (node (ref "IC4") (pin "15") (pinfunction "L8_15") (pintype "output"))
      (node (ref "R24") (pin "2") (pinfunction "2_2") (pintype "passive"))
    )
    (net (code "80") (name "SDI_MOSI") (class "Default")
      (node (ref "SERIAL") (pin "8") (pinfunction "8_8") (pintype "passive"))
    )
    (net (code "81") (name "SDI_SCLK") (class "Default")
      (node (ref "SERIAL") (pin "7") (pinfunction "7_7") (pintype "passive"))
    )
    (net (code "82") (name "SLIDER_IN") (class "Default")
      (node (ref "C6") (pin "1") (pinfunction "1_1") (pintype "passive"))
      (node (ref "JP1") (pin "2") (pinfunction "2_2") (pintype "passive"))
      (node (ref "JP2") (pin "2") (pinfunction "2_2") (pintype "passive"))
      (node (ref "POT1") (pin "2A") (pinfunction "S_2A") (pintype "passive"))
      (node (ref "SERIAL") (pin "5") (pinfunction "5_5") (pintype "passive"))
    )
    (net (code "83") (name "unconnected-(B10-PadL3)") (class "Default")
      (node (ref "B10") (pin "L3") (pinfunction "L3_L3") (pintype "bidirectional"))
    )
    (net (code "84") (name "unconnected-(B10-PadL4)") (class "Default")
      (node (ref "B10") (pin "L4") (pinfunction "L4_L4") (pintype "bidirectional"))
    )
    (net (code "85") (name "unconnected-(B10-PadLC2)") (class "Default")
      (node (ref "B10") (pin "LC2") (pinfunction "LC2_LC2") (pintype "bidirectional"))
    )
    (net (code "86") (name "unconnected-(B11-PadL3)") (class "Default")
      (node (ref "B11") (pin "L3") (pinfunction "L3_L3") (pintype "bidirectional"))
    )
    (net (code "87") (name "unconnected-(B11-PadL4)") (class "Default")
      (node (ref "B11") (pin "L4") (pinfunction "L4_L4") (pintype "bidirectional"))
    )
    (net (code "88") (name "unconnected-(B11-PadLC2)") (class "Default")
      (node (ref "B11") (pin "LC2") (pinfunction "LC2_LC2") (pintype "bidirectional"))
    )
    (net (code "89") (name "unconnected-(B12-PadL3)") (class "Default")
      (node (ref "B12") (pin "L3") (pinfunction "L3_L3") (pintype "bidirectional"))
    )
    (net (code "90") (name "unconnected-(B12-PadL4)") (class "Default")
      (node (ref "B12") (pin "L4") (pinfunction "L4_L4") (pintype "bidirectional"))
    )
    (net (code "91") (name "unconnected-(B12-PadLC2)") (class "Default")
      (node (ref "B12") (pin "LC2") (pinfunction "LC2_LC2") (pintype "bidirectional"))
    )
    (net (code "92") (name "unconnected-(B13-PadL3)") (class "Default")
      (node (ref "B13") (pin "L3") (pinfunction "L3_L3") (pintype "bidirectional"))
    )
    (net (code "93") (name "unconnected-(B13-PadL4)") (class "Default")
      (node (ref "B13") (pin "L4") (pinfunction "L4_L4") (pintype "bidirectional"))
    )
    (net (code "94") (name "unconnected-(B13-PadLC2)") (class "Default")
      (node (ref "B13") (pin "LC2") (pinfunction "LC2_LC2") (pintype "bidirectional"))
    )
    (net (code "95") (name "unconnected-(B14-PadL3)") (class "Default")
      (node (ref "B14") (pin "L3") (pinfunction "L3_L3") (pintype "bidirectional"))
    )
    (net (code "96") (name "unconnected-(B14-PadL4)") (class "Default")
      (node (ref "B14") (pin "L4") (pinfunction "L4_L4") (pintype "bidirectional"))
    )
    (net (code "97") (name "unconnected-(B14-PadLC2)") (class "Default")
      (node (ref "B14") (pin "LC2") (pinfunction "LC2_LC2") (pintype "bidirectional"))
    )
    (net (code "98") (name "unconnected-(B15-PadL3)") (class "Default")
      (node (ref "B15") (pin "L3") (pinfunction "L3_L3") (pintype "bidirectional"))
    )
    (net (code "99") (name "unconnected-(B15-PadL4)") (class "Default")
      (node (ref "B15") (pin "L4") (pinfunction "L4_L4") (pintype "bidirectional"))
    )
    (net (code "100") (name "unconnected-(B15-PadLC2)") (class "Default")
      (node (ref "B15") (pin "LC2") (pinfunction "LC2_LC2") (pintype "bidirectional"))
    )
    (net (code "101") (name "unconnected-(B16-PadL3)") (class "Default")
      (node (ref "B16") (pin "L3") (pinfunction "L3_L3") (pintype "bidirectional"))
    )
    (net (code "102") (name "unconnected-(B16-PadL4)") (class "Default")
      (node (ref "B16") (pin "L4") (pinfunction "L4_L4") (pintype "bidirectional"))
    )
    (net (code "103") (name "unconnected-(B16-PadLC2)") (class "Default")
      (node (ref "B16") (pin "LC2") (pinfunction "LC2_LC2") (pintype "bidirectional"))
    )
    (net (code "104") (name "unconnected-(B17-PadL3)") (class "Default")
      (node (ref "B17") (pin "L3") (pinfunction "L3_L3") (pintype "bidirectional"))
    )
    (net (code "105") (name "unconnected-(B17-PadL4)") (class "Default")
      (node (ref "B17") (pin "L4") (pinfunction "L4_L4") (pintype "bidirectional"))
    )
    (net (code "106") (name "unconnected-(B17-PadLC2)") (class "Default")
      (node (ref "B17") (pin "LC2") (pinfunction "LC2_LC2") (pintype "bidirectional"))
    )
    (net (code "107") (name "unconnected-(B18-PadL3)") (class "Default")
      (node (ref "B18") (pin "L3") (pinfunction "L3_L3") (pintype "bidirectional"))
    )
    (net (code "108") (name "unconnected-(B18-PadL4)") (class "Default")
      (node (ref "B18") (pin "L4") (pinfunction "L4_L4") (pintype "bidirectional"))
    )
    (net (code "109") (name "unconnected-(B18-PadLC2)") (class "Default")
      (node (ref "B18") (pin "LC2") (pinfunction "LC2_LC2") (pintype "bidirectional"))
    )
    (net (code "110") (name "unconnected-(IC1-GPB0-Pad1)") (class "Default")
      (node (ref "IC1") (pin "1") (pinfunction "GPB0_1") (pintype "bidirectional"))
    )
    (net (code "111") (name "unconnected-(IC1-GPB1-Pad2)") (class "Default")
      (node (ref "IC1") (pin "2") (pinfunction "GPB1_2") (pintype "bidirectional"))
    )
    (net (code "112") (name "unconnected-(IC1-GPB2-Pad3)") (class "Default")
      (node (ref "IC1") (pin "3") (pinfunction "GPB2_3") (pintype "bidirectional"))
    )
    (net (code "113") (name "unconnected-(IC1-GPB3-Pad4)") (class "Default")
      (node (ref "IC1") (pin "4") (pinfunction "GPB3_4") (pintype "bidirectional"))
    )
    (net (code "114") (name "unconnected-(IC1-GPB5-Pad6)") (class "Default")
      (node (ref "IC1") (pin "6") (pinfunction "GPB5_6") (pintype "bidirectional"))
    )
    (net (code "115") (name "unconnected-(IC1-GPB6-Pad7)") (class "Default")
      (node (ref "IC1") (pin "7") (pinfunction "GPB6_7") (pintype "bidirectional"))
    )
    (net (code "116") (name "unconnected-(IC1-GPB7-Pad8)") (class "Default")
      (node (ref "IC1") (pin "8") (pinfunction "GPB7_8") (pintype "bidirectional"))
    )
    (net (code "117") (name "unconnected-(IC1-INTA-Pad20)") (class "Default")
      (node (ref "IC1") (pin "20") (pinfunction "INTA_20") (pintype "output"))
    )
    (net (code "118") (name "unconnected-(IC1-INTB-Pad19)") (class "Default")
      (node (ref "IC1") (pin "19") (pinfunction "INTB_19") (pintype "output"))
    )
    (net (code "119") (name "unconnected-(IC3-L2-Pad8)") (class "Default")
      (node (ref "IC3") (pin "8") (pinfunction "L2_8") (pintype "output"))
    )
    (net (code "120") (name "unconnected-(IC3-L3-Pad9)") (class "Default")
      (node (ref "IC3") (pin "9") (pinfunction "L3_9") (pintype "output"))
    )
    (net (code "121") (name "unconnected-(IC3-L4-Pad10)") (class "Default")
      (node (ref "IC3") (pin "10") (pinfunction "L4_10") (pintype "output"))
    )
    (net (code "122") (name "unconnected-(IC3-L5-Pad11)") (class "Default")
      (node (ref "IC3") (pin "11") (pinfunction "L5_11") (pintype "output"))
    )
    (net (code "123") (name "unconnected-(IC3-L6-Pad12)") (class "Default")
      (node (ref "IC3") (pin "12") (pinfunction "L6_12") (pintype "output"))
    )
    (net (code "124") (name "unconnected-(IC3-L7-Pad13)") (class "Default")
      (node (ref "IC3") (pin "13") (pinfunction "L7_13") (pintype "output"))
    )
    (net (code "125") (name "unconnected-(IC3-L8-Pad15)") (class "Default")
      (node (ref "IC3") (pin "15") (pinfunction "L8_15") (pintype "output"))
    )
    (net (code "126") (name "unconnected-(IC3-L9-Pad16)") (class "Default")
      (node (ref "IC3") (pin "16") (pinfunction "L9_16") (pintype "output"))
    )
    (net (code "127") (name "unconnected-(IC3-L10-Pad17)") (class "Default")
      (node (ref "IC3") (pin "17") (pinfunction "L10_17") (pintype "output"))
    )
    (net (code "128") (name "unconnected-(IC3-L11-Pad18)") (class "Default")
      (node (ref "IC3") (pin "18") (pinfunction "L11_18") (pintype "output"))
    )
    (net (code "129") (name "unconnected-(IC3-L12-Pad19)") (class "Default")
      (node (ref "IC3") (pin "19") (pinfunction "L12_19") (pintype "output"))
    )
    (net (code "130") (name "unconnected-(IC3-L13-Pad20)") (class "Default")
      (node (ref "IC3") (pin "20") (pinfunction "L13_20") (pintype "output"))
    )
    (net (code "131") (name "unconnected-(IC3-L14-Pad21)") (class "Default")
      (node (ref "IC3") (pin "21") (pinfunction "L14_21") (pintype "output"))
    )
    (net (code "132") (name "unconnected-(IC3-L15-Pad22)") (class "Default")
      (node (ref "IC3") (pin "22") (pinfunction "L15_22") (pintype "output"))
    )
    (net (code "133") (name "unconnected-(IC4-L9-Pad16)") (class "Default")
      (node (ref "IC4") (pin "16") (pinfunction "L9_16") (pintype "output"))
    )
    (net (code "134") (name "unconnected-(IC4-L10-Pad17)") (class "Default")
      (node (ref "IC4") (pin "17") (pinfunction "L10_17") (pintype "output"))
    )
    (net (code "135") (name "unconnected-(IC4-L11-Pad18)") (class "Default")
      (node (ref "IC4") (pin "18") (pinfunction "L11_18") (pintype "output"))
    )
    (net (code "136") (name "unconnected-(IC4-L12-Pad19)") (class "Default")
      (node (ref "IC4") (pin "19") (pinfunction "L12_19") (pintype "output"))
    )
    (net (code "137") (name "unconnected-(IC4-L13-Pad20)") (class "Default")
      (node (ref "IC4") (pin "20") (pinfunction "L13_20") (pintype "output"))
    )
    (net (code "138") (name "unconnected-(IC4-L14-Pad21)") (class "Default")
      (node (ref "IC4") (pin "21") (pinfunction "L14_21") (pintype "output"))
    )
    (net (code "139") (name "unconnected-(IC4-L15-Pad22)") (class "Default")
      (node (ref "IC4") (pin "22") (pinfunction "L15_22") (pintype "output"))
    )
    (net (code "140") (name "unconnected-(IC5-GPB1-Pad2)") (class "Default")
      (node (ref "IC5") (pin "2") (pinfunction "GPB1_2") (pintype "bidirectional"))
    )
    (net (code "141") (name "unconnected-(IC5-GPB2-Pad3)") (class "Default")
      (node (ref "IC5") (pin "3") (pinfunction "GPB2_3") (pintype "bidirectional"))
    )
    (net (code "142") (name "unconnected-(IC5-GPB3-Pad4)") (class "Default")
      (node (ref "IC5") (pin "4") (pinfunction "GPB3_4") (pintype "bidirectional"))
    )
    (net (code "143") (name "unconnected-(IC5-GPB4-Pad5)") (class "Default")
      (node (ref "IC5") (pin "5") (pinfunction "GPB4_5") (pintype "bidirectional"))
    )
    (net (code "144") (name "unconnected-(IC5-GPB5-Pad6)") (class "Default")
      (node (ref "IC5") (pin "6") (pinfunction "GPB5_6") (pintype "bidirectional"))
    )
    (net (code "145") (name "unconnected-(IC5-GPB6-Pad7)") (class "Default")
      (node (ref "IC5") (pin "7") (pinfunction "GPB6_7") (pintype "bidirectional"))
    )
    (net (code "146") (name "unconnected-(IC5-GPB7-Pad8)") (class "Default")
      (node (ref "IC5") (pin "8") (pinfunction "GPB7_8") (pintype "bidirectional"))
    )
    (net (code "147") (name "unconnected-(IC5-INTA-Pad20)") (class "Default")
      (node (ref "IC5") (pin "20") (pinfunction "INTA_20") (pintype "output"))
    )
    (net (code "148") (name "unconnected-(IC5-INTB-Pad19)") (class "Default")
      (node (ref "IC5") (pin "19") (pinfunction "INTB_19") (pintype "output"))
    )
  )
)
